# Regulator.net
KiCad netlist of a schematic drawn in EAGLE
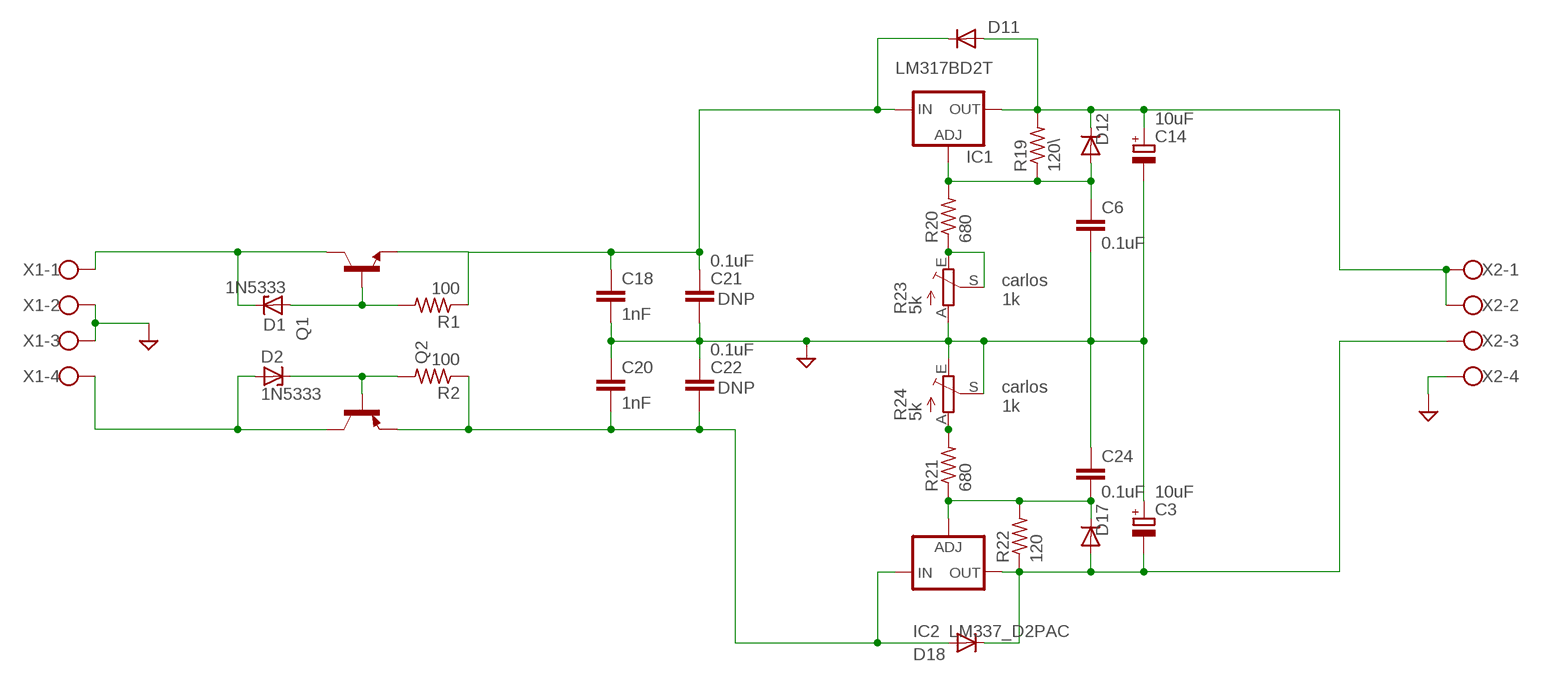
[diagram p0: schematic, sheet 1]

(export (version "E")
  (design (tool "Eeschema 10.0.6"))
  (components
    (comp (ref "C3")
      (value "10uF")
      (footprint "eagle-import:E2,5-6")
      (libsource (lib "eagle-import") (part "CPOL-EUE2.5-6"))
    )
    (comp (ref "C6")
      (value "0.1uF")
      (footprint "eagle-import:C025-025X050")
      (libsource (lib "eagle-import") (part "resistor_C-EU025-025X050"))
    )
    (comp (ref "C14")
      (value "10uF")
      (footprint "eagle-import:E2,5-6")
      (libsource (lib "eagle-import") (part "CPOL-EUE2.5-6"))
    )
    (comp (ref "C18")
      (value "1nF")
      (footprint "eagle-import:C025-025X050")
      (libsource (lib "eagle-import") (part "C-EU025-025X050"))
    )
    (comp (ref "C20")
      (value "1nF")
      (footprint "eagle-import:C025-025X050")
      (libsource (lib "eagle-import") (part "C-EU025-025X050"))
    )
    (comp (ref "C21")
      (value "0.1uF")
      (footprint "eagle-import:C025-025X050")
      (libsource (lib "eagle-import") (part "C-EU025-025X050"))
    )
    (comp (ref "C22")
      (value "0.1uF")
      (footprint "eagle-import:C025-025X050")
      (libsource (lib "eagle-import") (part "C-EU025-025X050"))
    )
    (comp (ref "C24")
      (value "0.1uF")
      (footprint "eagle-import:C025-025X050")
      (libsource (lib "eagle-import") (part "resistor_C-EU025-025X050"))
    )
    (comp (ref "D1")
      (value "1N5333")
      (footprint "eagle-import:C1702-15")
      (libsource (lib "eagle-import") (part "1N5333"))
    )
    (comp (ref "D2")
      (value "1N5333")
      (footprint "eagle-import:C1702-15")
      (libsource (lib "eagle-import") (part "1N5333"))
    )
    (comp (ref "D11")
      (value "1N4004")
      (footprint "eagle-import:1N4004")
      (libsource (lib "eagle-import") (part "1N4004"))
    )
    (comp (ref "D12")
      (value "1N4004")
      (footprint "eagle-import:1N4004")
      (libsource (lib "eagle-import") (part "1N4004"))
    )
    (comp (ref "D17")
      (value "1N4004")
      (footprint "eagle-import:1N4004")
      (libsource (lib "eagle-import") (part "1N4004"))
    )
    (comp (ref "D18")
      (value "1N4004")
      (footprint "eagle-import:1N4004")
      (libsource (lib "eagle-import") (part "1N4004"))
    )
    (comp (ref "IC1")
      (value "LM317BD2T")
      (footprint "eagle-import:D2PACK")
      (libsource (lib "eagle-import") (part "LM317?BD2T"))
    )
    (comp (ref "IC2")
      (value "LM337_D2PAC")
      (footprint "eagle-import:D2PACK")
      (libsource (lib "eagle-import") (part "LM337_D2PAC"))
    )
    (comp (ref "Q1")
      (value "-NPN-TO220V")
      (footprint "eagle-import:TO220V")
      (libsource (lib "eagle-import") (part "-NPN-TO220V"))
    )
    (comp (ref "Q2")
      (value "-PNP-TO220V")
      (footprint "eagle-import:TO220V")
      (libsource (lib "eagle-import") (part "-PNP-TO220V"))
    )
    (comp (ref "R1")
      (value "100")
      (footprint "eagle-import:0309_12")
      (libsource (lib "eagle-import") (part "R-US_0309/12"))
    )
    (comp (ref "R2")
      (value "100")
      (footprint "eagle-import:0309_12")
      (libsource (lib "eagle-import") (part "R-US_0309/12"))
    )
    (comp (ref "R19")
      (value "120\\")
      (footprint "eagle-import:0309V")
      (libsource (lib "eagle-import") (part "R-US_0309/V"))
    )
    (comp (ref "R20")
      (value "680")
      (footprint "eagle-import:0309V")
      (libsource (lib "eagle-import") (part "R-US_0309/V"))
    )
    (comp (ref "R21")
      (value "680")
      (footprint "eagle-import:0309V")
      (libsource (lib "eagle-import") (part "R-US_0309/V"))
    )
    (comp (ref "R22")
      (value "120")
      (footprint "eagle-import:0309V")
      (libsource (lib "eagle-import") (part "R-US_0309/V"))
    )
    (comp (ref "R23")
      (value "5k")
      (footprint "eagle-import:B25P")
      (libsource (lib "eagle-import") (part "TRIM_EU-B25P"))
    )
    (comp (ref "R24")
      (value "5k")
      (footprint "eagle-import:B25P")
      (libsource (lib "eagle-import") (part "TRIM_EU-B25P"))
    )
    (comp (ref "X1")
      (value "W237-4")
      (footprint "eagle-import:W237-4")
      (libsource (lib "eagle-import") (part "W237-4"))
    )
    (comp (ref "X2")
      (value "W237-4")
      (footprint "eagle-import:W237-4")
      (libsource (lib "eagle-import") (part "W237-4"))
    )
  )
  (nets
    (net (code "1") (name "Net-(IC1-ADJ)") (class "Default")
      (node (ref "C6") (pin "1") (pinfunction "1_1") (pintype "passive"))
      (node (ref "D12") (pin "A") (pinfunction "A_A") (pintype "passive"))
      (node (ref "IC1") (pin "1") (pinfunction "ADJ_1") (pintype "input"))
      (node (ref "R19") (pin "1") (pinfunction "1_1") (pintype "passive"))
      (node (ref "R20") (pin "2") (pinfunction "2_2") (pintype "passive"))
    )
    (net (code "2") (name "Net-(IC1-IN)") (class "Default")
      (node (ref "C18") (pin "1") (pinfunction "1_1") (pintype "passive"))
      (node (ref "C21") (pin "1") (pinfunction "1_1") (pintype "passive"))
      (node (ref "D11") (pin "C") (pinfunction "C_C") (pintype "passive"))
      (node (ref "IC1") (pin "3") (pinfunction "IN_3") (pintype "input"))
      (node (ref "Q1") (pin "3") (pinfunction "E_3") (pintype "passive"))
      (node (ref "R1") (pin "1") (pinfunction "1_1") (pintype "passive"))
    )
    (net (code "3") (name "Net-(IC1-OUT)") (class "Default")
      (node (ref "C14") (pin "+") (pinfunction "+_+") (pintype "passive"))
      (node (ref "D11") (pin "A") (pinfunction "A_A") (pintype "passive"))
      (node (ref "D12") (pin "C") (pinfunction "C_C") (pintype "passive"))
      (node (ref "IC1") (pin "2") (pinfunction "OUT_2") (pintype "passive"))
      (node (ref "R19") (pin "2") (pinfunction "2_2") (pintype "passive"))
      (node (ref "X2") (pin "1") (pinfunction "KL_1") (pintype "passive"))
      (node (ref "X2") (pin "2") (pinfunction "KL_2") (pintype "passive"))
    )
    (net (code "4") (name "Net-(IC2-ADJ)") (class "Default")
      (node (ref "C24") (pin "2") (pinfunction "2_2") (pintype "passive"))
      (node (ref "D17") (pin "C") (pinfunction "C_C") (pintype "passive"))
      (node (ref "IC2") (pin "1") (pinfunction "ADJ_1") (pintype "input"))
      (node (ref "R21") (pin "1") (pinfunction "1_1") (pintype "passive"))
      (node (ref "R22") (pin "2") (pinfunction "2_2") (pintype "passive"))
    )
    (net (code "5") (name "Net-(IC2-IN)") (class "Default")
      (node (ref "C20") (pin "2") (pinfunction "2_2") (pintype "passive"))
      (node (ref "C22") (pin "2") (pinfunction "2_2") (pintype "passive"))
      (node (ref "D18") (pin "A") (pinfunction "A_A") (pintype "passive"))
      (node (ref "IC2") (pin "3") (pinfunction "IN_3") (pintype "input"))
      (node (ref "Q2") (pin "3") (pinfunction "E_3") (pintype "passive"))
      (node (ref "R2") (pin "1") (pinfunction "1_1") (pintype "passive"))
    )
    (net (code "6") (name "Net-(IC2-OUT)") (class "Default")
      (node (ref "C3") (pin "-") (pinfunction "-_-") (pintype "passive"))
      (node (ref "D17") (pin "A") (pinfunction "A_A") (pintype "passive"))
      (node (ref "D18") (pin "C") (pinfunction "C_C") (pintype "passive"))
      (node (ref "IC2") (pin "2") (pinfunction "OUT_2") (pintype "passive"))
      (node (ref "R22") (pin "1") (pinfunction "1_1") (pintype "passive"))
      (node (ref "X2") (pin "3") (pinfunction "KL_3") (pintype "passive"))
    )
    (net (code "7") (name "Net-(Q1-B)") (class "Default")
      (node (ref "D1") (pin "A") (pinfunction "A_A") (pintype "passive"))
      (node (ref "Q1") (pin "1") (pinfunction "B_1") (pintype "passive"))
      (node (ref "R1") (pin "2") (pinfunction "2_2") (pintype "passive"))
    )
    (net (code "8") (name "Net-(Q1-C)") (class "Default")
      (node (ref "D1") (pin "C") (pinfunction "C_C") (pintype "passive"))
      (node (ref "Q1") (pin "2") (pinfunction "C_2") (pintype "passive"))
      (node (ref "X1") (pin "1") (pinfunction "KL_1") (pintype "passive"))
    )
    (net (code "9") (name "Net-(Q2-B)") (class "Default")
      (node (ref "D2") (pin "C") (pinfunction "C_C") (pintype "passive"))
      (node (ref "Q2") (pin "1") (pinfunction "B_1") (pintype "passive"))
      (node (ref "R2") (pin "2") (pinfunction "2_2") (pintype "passive"))
    )
    (net (code "10") (name "Net-(Q2-C)") (class "Default")
      (node (ref "D2") (pin "A") (pinfunction "A_A") (pintype "passive"))
      (node (ref "Q2") (pin "2") (pinfunction "C_2") (pintype "passive"))
      (node (ref "X1") (pin "4") (pinfunction "KL_4") (pintype "passive"))
    )
    (net (code "11") (name "Net-(R20-Pad1)") (class "Default")
      (node (ref "R20") (pin "1") (pinfunction "1_1") (pintype "passive"))
      (node (ref "R23") (pin "E") (pinfunction "E_E") (pintype "passive"))
      (node (ref "R23") (pin "S") (pinfunction "S_S") (pintype "passive"))
    )
    (net (code "12") (name "Net-(R21-Pad2)") (class "Default")
      (node (ref "R21") (pin "2") (pinfunction "2_2") (pintype "passive"))
      (node (ref "R24") (pin "A") (pinfunction "A_A") (pintype "passive"))
    )
    (net (code "13") (name "SGND") (class "Default")
      (node (ref "C14") (pin "-") (pinfunction "-_-") (pintype "passive"))
      (node (ref "C18") (pin "2") (pinfunction "2_2") (pintype "passive"))
      (node (ref "C20") (pin "1") (pinfunction "1_1") (pintype "passive"))
      (node (ref "C21") (pin "2") (pinfunction "2_2") (pintype "passive"))
      (node (ref "C22") (pin "1") (pinfunction "1_1") (pintype "passive"))
      (node (ref "C24") (pin "1") (pinfunction "1_1") (pintype "passive"))
      (node (ref "C3") (pin "+") (pinfunction "+_+") (pintype "passive"))
      (node (ref "C6") (pin "2") (pinfunction "2_2") (pintype "passive"))
      (node (ref "R23") (pin "A") (pinfunction "A_A") (pintype "passive"))
      (node (ref "R24") (pin "E") (pinfunction "E_E") (pintype "passive"))
      (node (ref "R24") (pin "S") (pinfunction "S_S") (pintype "passive"))
      (node (ref "X1") (pin "2") (pinfunction "KL_2") (pintype "passive"))
      (node (ref "X1") (pin "3") (pinfunction "KL_3") (pintype "passive"))
      (node (ref "X2") (pin "4") (pinfunction "KL_4") (pintype "passive"))
    )
  )
)
